# Adafruit_ESP8266_Feather.net
KiCad netlist of a schematic drawn in EAGLE
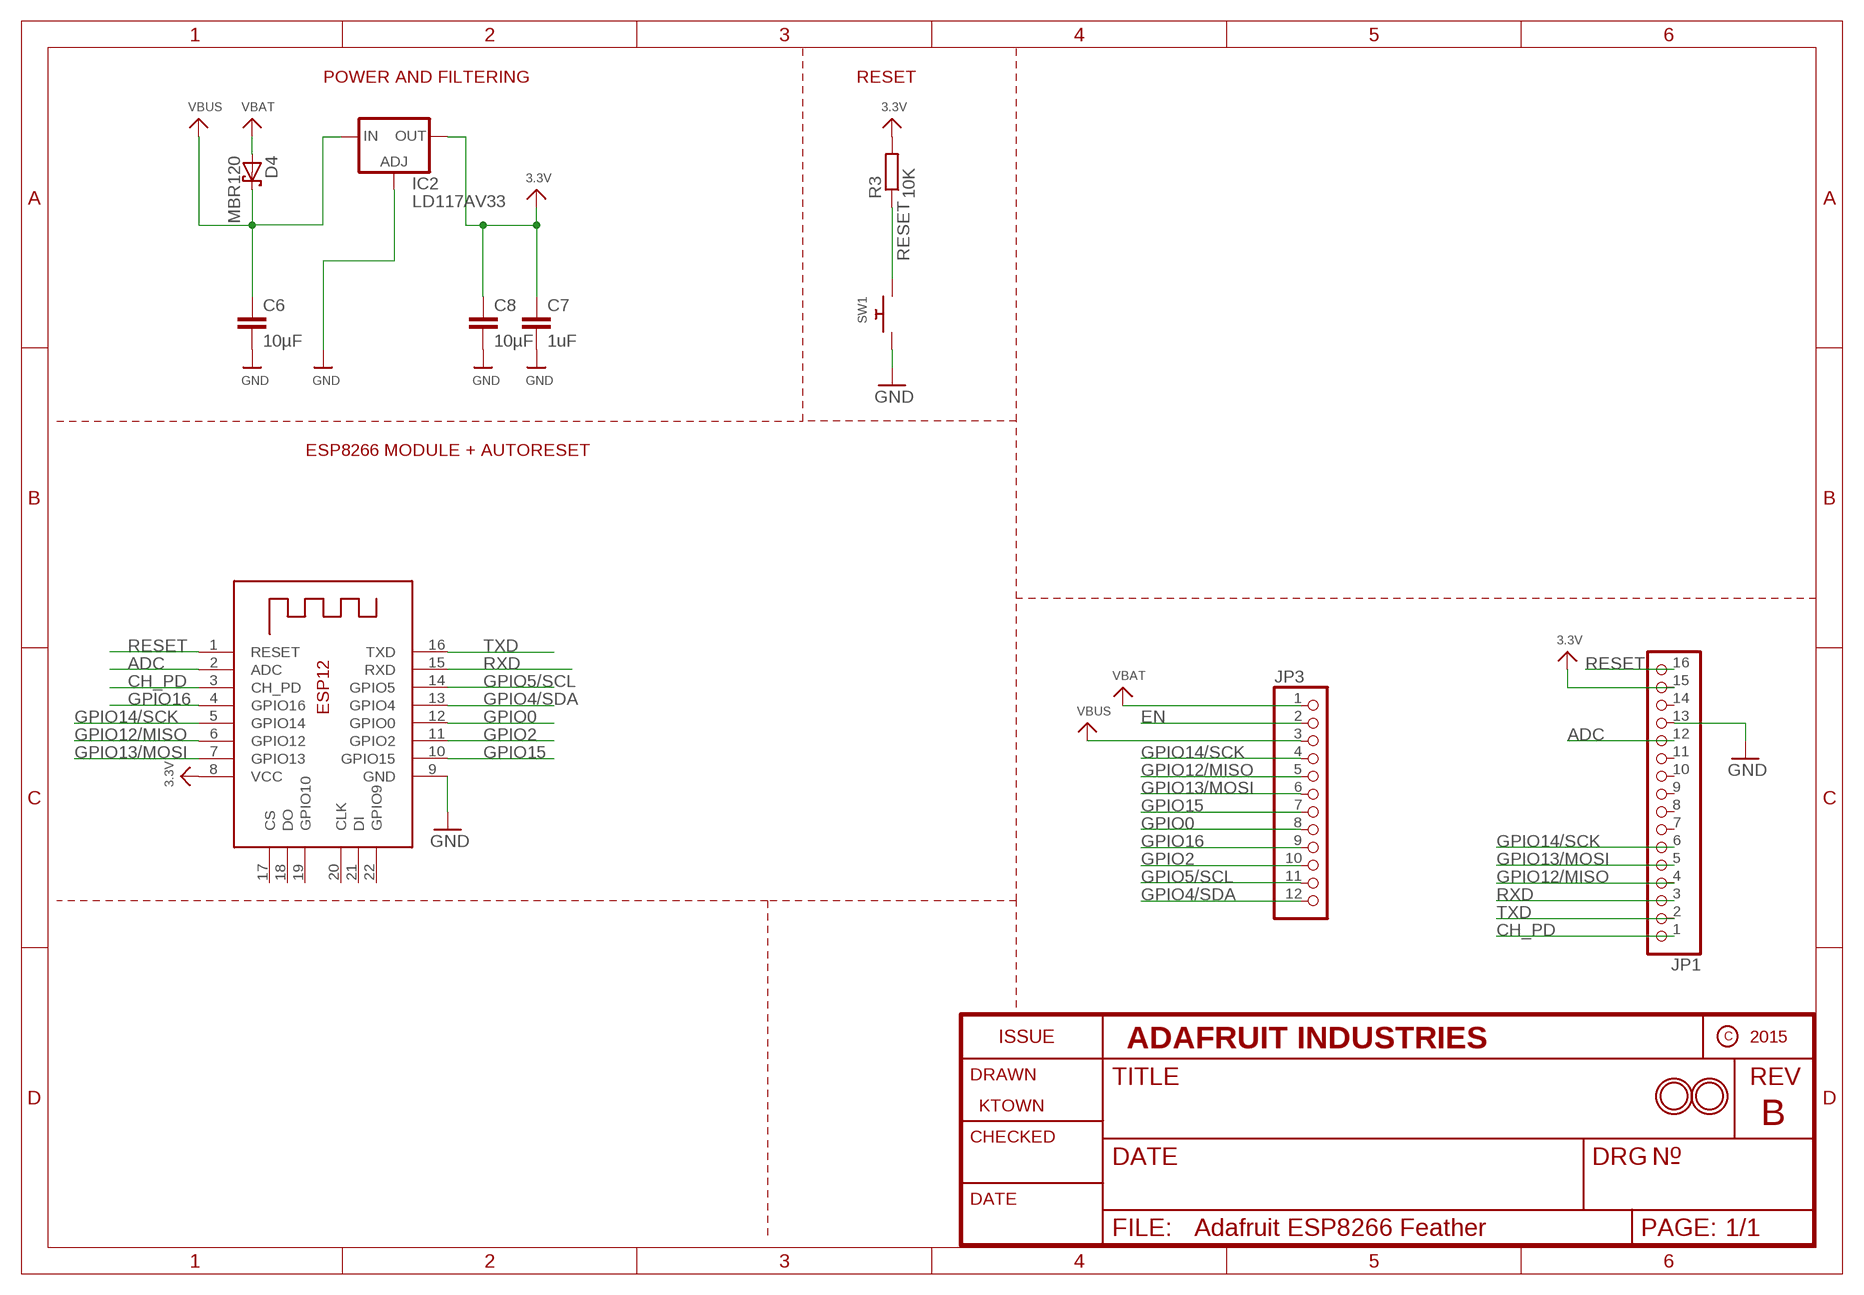
[diagram p0: schematic, sheet 1]

(export (version "E")
  (design (tool "Eeschema 10.0.6"))
  (components
    (comp (ref "C6")
      (value "10µF")
      (footprint "eagle-import:C025-024X044")
      (libsource (lib "eagle-import") (part "C-EU025-024X044"))
    )
    (comp (ref "C7")
      (value "1uF")
      (footprint "eagle-import:C025-024X044")
      (libsource (lib "eagle-import") (part "C-EU025-024X044"))
    )
    (comp (ref "C8")
      (value "10µF")
      (footprint "eagle-import:C025-024X044")
      (libsource (lib "eagle-import") (part "C-EU025-024X044"))
    )
    (comp (ref "D4")
      (value "MBR120")
      (footprint "eagle-import:DO41-7")
      (libsource (lib "eagle-import") (part "SCHOTTKY-DIODEDO41-7"))
    )
    (comp (ref "IC2")
      (value "LD117AV33")
      (footprint "eagle-import:TO220L1")
      (libsource (lib "eagle-import") (part "LD117A?V33"))
    )
    (comp (ref "JP1")
      (value "HEADER-1X16ROUND")
      (footprint "eagle-import:1X16_ROUND")
      (libsource (lib "eagle-import") (part "HEADER-1X16ROUND"))
    )
    (comp (ref "JP3")
      (value "HEADER-1X12")
      (footprint "eagle-import:1X12_ROUND")
      (libsource (lib "eagle-import") (part "HEADER-1X12"))
    )
    (comp (ref "R3")
      (value "10K")
      (footprint "eagle-import:0204_5")
      (libsource (lib "eagle-import") (part "R-EU_0204/5"))
    )
    (comp (ref "SW1")
      (value "SWITCH_PUSHBUTTONEVQ-PE")
      (footprint "eagle-import:TACT_PANA-EVQ")
      (libsource (lib "eagle-import") (part "SWITCH_PUSHBUTTONEVQ-PE"))
    )
    (comp (ref "U$31")
      (value "MOUNTINGHOLE2.5")
      (footprint "eagle-import:MOUNTINGHOLE_2.5_PLATED")
      (libsource (lib "eagle-import") (part "MOUNTINGHOLE2.5"))
    )
    (comp (ref "U$32")
      (value "MOUNTINGHOLE2.5")
      (footprint "eagle-import:MOUNTINGHOLE_2.5_PLATED")
      (libsource (lib "eagle-import") (part "MOUNTINGHOLE2.5"))
    )
    (comp (ref "X2")
      (value "ESP-12")
      (footprint "eagle-import:ESP-12E")
      (libsource (lib "eagle-import") (part "ESP-12E"))
    )
  )
  (nets
    (net (code "1") (name "/ADC") (class "Default")
      (node (ref "JP1") (pin "12") (pinfunction "12_12") (pintype "passive"))
      (node (ref "X2") (pin "2") (pinfunction "ADC_2") (pintype "passive"))
    )
    (net (code "2") (name "/CH_PD") (class "Default")
      (node (ref "JP1") (pin "1") (pinfunction "1_1") (pintype "passive"))
      (node (ref "X2") (pin "3") (pinfunction "CH_PD_3") (pintype "input"))
    )
    (net (code "3") (name "/EN") (class "Default")
      (node (ref "JP3") (pin "2") (pinfunction "2_2") (pintype "passive"))
    )
    (net (code "4") (name "/GPIO0") (class "Default")
      (node (ref "JP3") (pin "8") (pinfunction "8_8") (pintype "passive"))
      (node (ref "X2") (pin "12") (pinfunction "GPIO0_12") (pintype "bidirectional"))
    )
    (net (code "5") (name "/GPIO2") (class "Default")
      (node (ref "JP3") (pin "10") (pinfunction "10_10") (pintype "passive"))
      (node (ref "X2") (pin "11") (pinfunction "GPIO2_11") (pintype "bidirectional"))
    )
    (net (code "6") (name "/GPIO4{slash}SDA") (class "Default")
      (node (ref "JP3") (pin "12") (pinfunction "12_12") (pintype "passive"))
      (node (ref "X2") (pin "13") (pinfunction "GPIO4_13") (pintype "bidirectional"))
    )
    (net (code "7") (name "/GPIO5{slash}SCL") (class "Default")
      (node (ref "JP3") (pin "11") (pinfunction "11_11") (pintype "passive"))
      (node (ref "X2") (pin "14") (pinfunction "GPIO5_14") (pintype "bidirectional"))
    )
    (net (code "8") (name "/GPIO12{slash}MISO") (class "Default")
      (node (ref "JP1") (pin "4") (pinfunction "4_4") (pintype "passive"))
      (node (ref "JP3") (pin "5") (pinfunction "5_5") (pintype "passive"))
      (node (ref "X2") (pin "6") (pinfunction "GPIO12_6") (pintype "bidirectional"))
    )
    (net (code "9") (name "/GPIO13{slash}MOSI") (class "Default")
      (node (ref "JP1") (pin "5") (pinfunction "5_5") (pintype "passive"))
      (node (ref "JP3") (pin "6") (pinfunction "6_6") (pintype "passive"))
      (node (ref "X2") (pin "7") (pinfunction "GPIO13_7") (pintype "bidirectional"))
    )
    (net (code "10") (name "/GPIO14{slash}SCK") (class "Default")
      (node (ref "JP1") (pin "6") (pinfunction "6_6") (pintype "passive"))
      (node (ref "JP3") (pin "4") (pinfunction "4_4") (pintype "passive"))
      (node (ref "X2") (pin "5") (pinfunction "GPIO14_5") (pintype "bidirectional"))
    )
    (net (code "11") (name "/GPIO15") (class "Default")
      (node (ref "JP3") (pin "7") (pinfunction "7_7") (pintype "passive"))
      (node (ref "X2") (pin "10") (pinfunction "GPIO15_10") (pintype "bidirectional"))
    )
    (net (code "12") (name "/GPIO16") (class "Default")
      (node (ref "JP3") (pin "9") (pinfunction "9_9") (pintype "passive"))
      (node (ref "X2") (pin "4") (pinfunction "GPIO16_4") (pintype "bidirectional"))
    )
    (net (code "13") (name "/RESET") (class "Default")
      (node (ref "JP1") (pin "16") (pinfunction "16_16") (pintype "passive"))
      (node (ref "R3") (pin "1") (pinfunction "1_1") (pintype "passive"))
      (node (ref "SW1") (pin "P$1") (pinfunction "P$1_P$1") (pintype "passive"))
      (node (ref "X2") (pin "1") (pinfunction "RESET_1") (pintype "input"))
    )
    (net (code "14") (name "/RXD") (class "Default")
      (node (ref "JP1") (pin "3") (pinfunction "3_3") (pintype "passive"))
      (node (ref "X2") (pin "15") (pinfunction "RXD_15") (pintype "input"))
    )
    (net (code "15") (name "/TXD") (class "Default")
      (node (ref "JP1") (pin "2") (pinfunction "2_2") (pintype "passive"))
      (node (ref "X2") (pin "16") (pinfunction "TXD_16") (pintype "output"))
    )
    (net (code "16") (name "3.3V") (class "Default")
      (node (ref "C7") (pin "1") (pinfunction "1_1") (pintype "passive"))
      (node (ref "C8") (pin "1") (pinfunction "1_1") (pintype "passive"))
      (node (ref "IC2") (pin "2") (pinfunction "OUT_2") (pintype "passive"))
      (node (ref "JP1") (pin "15") (pinfunction "15_15") (pintype "passive"))
      (node (ref "R3") (pin "2") (pinfunction "2_2") (pintype "passive"))
      (node (ref "X2") (pin "8") (pinfunction "VCC_8") (pintype "power_in"))
    )
    (net (code "17") (name "GND") (class "Default")
      (node (ref "C6") (pin "2") (pinfunction "2_2") (pintype "passive"))
      (node (ref "C7") (pin "2") (pinfunction "2_2") (pintype "passive"))
      (node (ref "C8") (pin "2") (pinfunction "2_2") (pintype "passive"))
      (node (ref "IC2") (pin "1") (pinfunction "ADJ_1") (pintype "input"))
      (node (ref "JP1") (pin "13") (pinfunction "13_13") (pintype "passive"))
      (node (ref "SW1") (pin "P$2") (pinfunction "P$2_P$2") (pintype "passive"))
      (node (ref "X2") (pin "9") (pinfunction "GND_9") (pintype "power_in"))
    )
    (net (code "18") (name "VBAT") (class "Default")
      (node (ref "D4") (pin "A") (pinfunction "A_A") (pintype "passive"))
      (node (ref "JP3") (pin "1") (pinfunction "1_1") (pintype "passive"))
    )
    (net (code "19") (name "VBUS") (class "Default")
      (node (ref "C6") (pin "1") (pinfunction "1_1") (pintype "passive"))
      (node (ref "D4") (pin "C") (pinfunction "C_C") (pintype "passive"))
      (node (ref "IC2") (pin "3") (pinfunction "IN_3") (pintype "input"))
      (node (ref "JP3") (pin "3") (pinfunction "3_3") (pintype "passive"))
    )
    (net (code "20") (name "unconnected-(JP1-Pad7)") (class "Default")
      (node (ref "JP1") (pin "7") (pinfunction "7_7") (pintype "passive"))
    )
    (net (code "21") (name "unconnected-(JP1-Pad8)") (class "Default")
      (node (ref "JP1") (pin "8") (pinfunction "8_8") (pintype "passive"))
    )
    (net (code "22") (name "unconnected-(JP1-Pad9)") (class "Default")
      (node (ref "JP1") (pin "9") (pinfunction "9_9") (pintype "passive"))
    )
    (net (code "23") (name "unconnected-(JP1-Pad10)") (class "Default")
      (node (ref "JP1") (pin "10") (pinfunction "10_10") (pintype "passive"))
    )
    (net (code "24") (name "unconnected-(JP1-Pad11)") (class "Default")
      (node (ref "JP1") (pin "11") (pinfunction "11_11") (pintype "passive"))
    )
    (net (code "25") (name "unconnected-(JP1-Pad14)") (class "Default")
      (node (ref "JP1") (pin "14") (pinfunction "14_14") (pintype "passive"))
    )
    (net (code "26") (name "unconnected-(X2-CLK-Pad20)") (class "Default")
      (node (ref "X2") (pin "20") (pinfunction "CLK_20") (pintype "bidirectional"))
    )
    (net (code "27") (name "unconnected-(X2-CS-Pad17)") (class "Default")
      (node (ref "X2") (pin "17") (pinfunction "CS_17") (pintype "bidirectional"))
    )
    (net (code "28") (name "unconnected-(X2-DI-Pad21)") (class "Default")
      (node (ref "X2") (pin "21") (pinfunction "DI_21") (pintype "bidirectional"))
    )
    (net (code "29") (name "unconnected-(X2-DO-Pad18)") (class "Default")
      (node (ref "X2") (pin "18") (pinfunction "DO_18") (pintype "bidirectional"))
    )
    (net (code "30") (name "unconnected-(X2-GPIO9-Pad22)") (class "Default")
      (node (ref "X2") (pin "22") (pinfunction "GPIO9_22") (pintype "bidirectional"))
    )
    (net (code "31") (name "unconnected-(X2-GPIO10-Pad19)") (class "Default")
      (node (ref "X2") (pin "19") (pinfunction "GPIO10_19") (pintype "bidirectional"))
    )
  )
)
